# team_dashboard_display.net
KiCad netlist of a schematic drawn in EAGLE
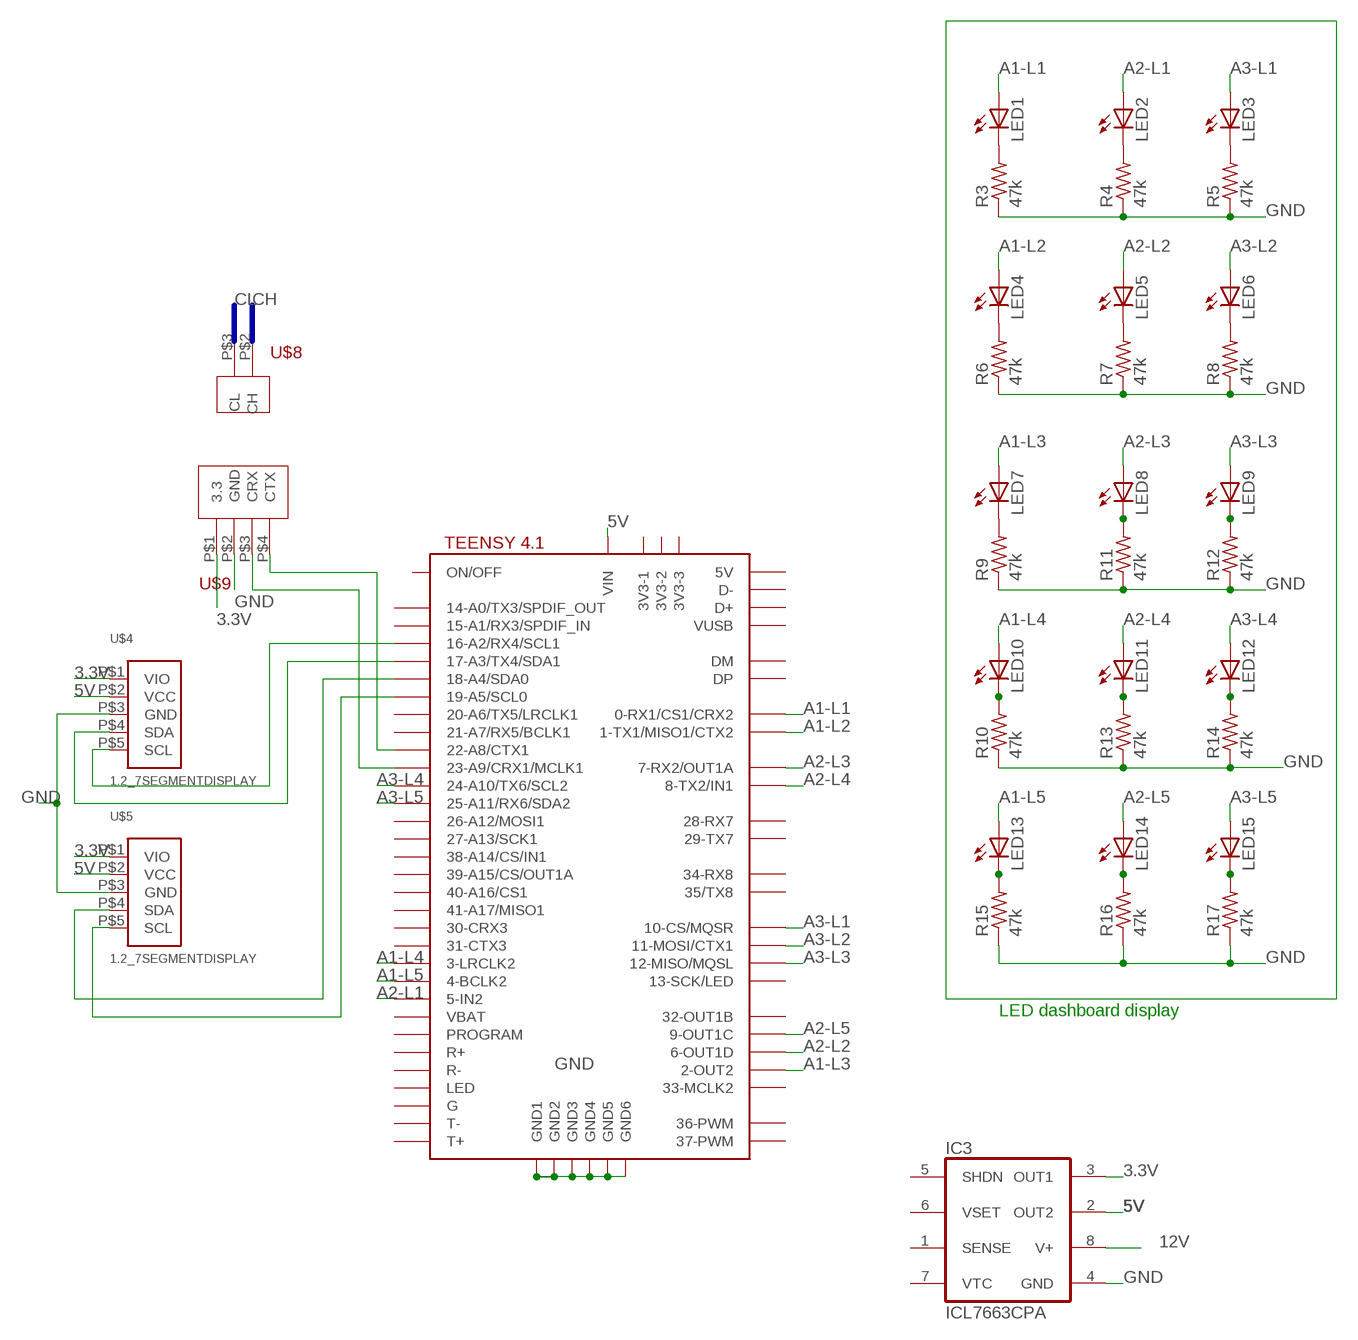
[diagram p0: schematic, sheet 1]

(export (version "E")
  (design (tool "Eeschema 10.0.6"))
  (components
    (comp (ref "IC3")
      (value "ICL7663CPA")
      (footprint "eagle-import:DIL08")
      (libsource (lib "eagle-import") (part "ICL7663CPA"))
    )
    (comp (ref "LED1")
      (value "LED3MM")
      (footprint "eagle-import:LED3MM")
      (libsource (lib "eagle-import") (part "LED3MM"))
    )
    (comp (ref "LED2")
      (value "LED3MM")
      (footprint "eagle-import:LED3MM")
      (libsource (lib "eagle-import") (part "LED3MM"))
    )
    (comp (ref "LED3")
      (value "LED3MM")
      (footprint "eagle-import:LED3MM")
      (libsource (lib "eagle-import") (part "LED3MM"))
    )
    (comp (ref "LED4")
      (value "LED3MM")
      (footprint "eagle-import:LED3MM")
      (libsource (lib "eagle-import") (part "LED3MM"))
    )
    (comp (ref "LED5")
      (value "LED3MM")
      (footprint "eagle-import:LED3MM")
      (libsource (lib "eagle-import") (part "LED3MM"))
    )
    (comp (ref "LED6")
      (value "LED3MM")
      (footprint "eagle-import:LED3MM")
      (libsource (lib "eagle-import") (part "LED3MM"))
    )
    (comp (ref "LED7")
      (value "LED3MM")
      (footprint "eagle-import:LED3MM")
      (libsource (lib "eagle-import") (part "LED3MM"))
    )
    (comp (ref "LED8")
      (value "LED3MM")
      (footprint "eagle-import:LED3MM")
      (libsource (lib "eagle-import") (part "LED3MM"))
    )
    (comp (ref "LED9")
      (value "LED3MM")
      (footprint "eagle-import:LED3MM")
      (libsource (lib "eagle-import") (part "LED3MM"))
    )
    (comp (ref "LED10")
      (value "LED3MM")
      (footprint "eagle-import:LED3MM")
      (libsource (lib "eagle-import") (part "LED3MM"))
    )
    (comp (ref "LED11")
      (value "LED3MM")
      (footprint "eagle-import:LED3MM")
      (libsource (lib "eagle-import") (part "LED3MM"))
    )
    (comp (ref "LED12")
      (value "LED3MM")
      (footprint "eagle-import:LED3MM")
      (libsource (lib "eagle-import") (part "LED3MM"))
    )
    (comp (ref "LED13")
      (value "LED3MM")
      (footprint "eagle-import:LED3MM")
      (libsource (lib "eagle-import") (part "LED3MM"))
    )
    (comp (ref "LED14")
      (value "LED3MM")
      (footprint "eagle-import:LED3MM")
      (libsource (lib "eagle-import") (part "LED3MM"))
    )
    (comp (ref "LED15")
      (value "LED3MM")
      (footprint "eagle-import:LED3MM")
      (libsource (lib "eagle-import") (part "LED3MM"))
    )
    (comp (ref "R3")
      (value "47k")
      (footprint "eagle-import:0204_7")
      (libsource (lib "eagle-import") (part "R-US_0204/7"))
    )
    (comp (ref "R4")
      (value "47k")
      (footprint "eagle-import:0204_7")
      (libsource (lib "eagle-import") (part "R-US_0204/7"))
    )
    (comp (ref "R5")
      (value "47k")
      (footprint "eagle-import:0204_7")
      (libsource (lib "eagle-import") (part "R-US_0204/7"))
    )
    (comp (ref "R6")
      (value "47k")
      (footprint "eagle-import:0204_7")
      (libsource (lib "eagle-import") (part "R-US_0204/7"))
    )
    (comp (ref "R7")
      (value "47k")
      (footprint "eagle-import:0204_7")
      (libsource (lib "eagle-import") (part "R-US_0204/7"))
    )
    (comp (ref "R8")
      (value "47k")
      (footprint "eagle-import:0204_7")
      (libsource (lib "eagle-import") (part "R-US_0204/7"))
    )
    (comp (ref "R9")
      (value "47k")
      (footprint "eagle-import:0204_7")
      (libsource (lib "eagle-import") (part "R-US_0204/7"))
    )
    (comp (ref "R10")
      (value "47k")
      (footprint "eagle-import:0204_7")
      (libsource (lib "eagle-import") (part "R-US_0204/7"))
    )
    (comp (ref "R11")
      (value "47k")
      (footprint "eagle-import:0204_7")
      (libsource (lib "eagle-import") (part "R-US_0204/7"))
    )
    (comp (ref "R12")
      (value "47k")
      (footprint "eagle-import:0204_7")
      (libsource (lib "eagle-import") (part "R-US_0204/7"))
    )
    (comp (ref "R13")
      (value "47k")
      (footprint "eagle-import:0204_7")
      (libsource (lib "eagle-import") (part "R-US_0204/7"))
    )
    (comp (ref "R14")
      (value "47k")
      (footprint "eagle-import:0204_7")
      (libsource (lib "eagle-import") (part "R-US_0204/7"))
    )
    (comp (ref "R15")
      (value "47k")
      (footprint "eagle-import:0204_7")
      (libsource (lib "eagle-import") (part "R-US_0204/7"))
    )
    (comp (ref "R16")
      (value "47k")
      (footprint "eagle-import:0204_7")
      (libsource (lib "eagle-import") (part "R-US_0204/7"))
    )
    (comp (ref "R17")
      (value "47k")
      (footprint "eagle-import:0204_7")
      (libsource (lib "eagle-import") (part "R-US_0204/7"))
    )
    (comp (ref "U$2")
      (value "TEENSY41")
      (footprint "eagle-import:TEENSY41")
      (libsource (lib "eagle-import") (part "TEENSY41"))
    )
    (comp (ref "U$4")
      (value "1.2_7SEGMENTDISPLAY")
      (footprint "eagle-import:5IL")
      (libsource (lib "eagle-import") (part "1.2_7SEGMENTDISPLAY"))
    )
    (comp (ref "U$5")
      (value "1.2_7SEGMENTDISPLAY")
      (footprint "eagle-import:5IL")
      (libsource (lib "eagle-import") (part "1.2_7SEGMENTDISPLAY"))
    )
    (comp (ref "U$8")
      (value "CAN_BUS")
      (footprint "eagle-import:CAN_BUS")
      (libsource (lib "eagle-import") (part "CAN_BUS"))
    )
    (comp (ref "U$9")
      (value "CAN_TEE")
      (footprint "eagle-import:CAN_TEN")
      (libsource (lib "eagle-import") (part "CAN_TEE"))
    )
  )
  (nets
    (net (code "3") (name "/3.3V") (class "Default")
      (node (ref "IC3") (pin "3") (pinfunction "OUT1_3") (pintype "output"))
      (node (ref "U$4") (pin "P$1") (pinfunction "VIO_P$1") (pintype "bidirectional"))
      (node (ref "U$5") (pin "P$1") (pinfunction "VIO_P$1") (pintype "bidirectional"))
      (node (ref "U$9") (pin "P$1") (pinfunction "3.3_P$1") (pintype "bidirectional"))
    )
    (net (code "4") (name "/5V") (class "Default")
      (node (ref "IC3") (pin "2") (pinfunction "OUT2_2") (pintype "output"))
      (node (ref "U$2") (pin "VIN") (pinfunction "VIN_VIN") (pintype "bidirectional"))
      (node (ref "U$4") (pin "P$2") (pinfunction "VCC_P$2") (pintype "bidirectional"))
      (node (ref "U$5") (pin "P$2") (pinfunction "VCC_P$2") (pintype "bidirectional"))
    )
    (net (code "5") (name "/12V") (class "Default")
      (node (ref "IC3") (pin "8") (pinfunction "V+_8") (pintype "power_in"))
    )
    (net (code "6") (name "/A1-L1") (class "Default")
      (node (ref "LED1") (pin "A") (pinfunction "A_A") (pintype "passive"))
      (node (ref "U$2") (pin "0-RX1/CS1/CRX2") (pinfunction "0-RX1/CS1/CRX2_0-RX1/CS1/CRX2") (pintype "bidirectional"))
    )
    (net (code "7") (name "/A1-L2") (class "Default")
      (node (ref "LED4") (pin "A") (pinfunction "A_A") (pintype "passive"))
      (node (ref "U$2") (pin "1-TX1/MISO1/CTX2") (pinfunction "1-TX1/MISO1/CTX2_1-TX1/MISO1/CTX2") (pintype "bidirectional"))
    )
    (net (code "8") (name "/A1-L3") (class "Default")
      (node (ref "LED7") (pin "A") (pinfunction "A_A") (pintype "passive"))
      (node (ref "U$2") (pin "2-OUT2") (pinfunction "2-OUT2_2-OUT2") (pintype "bidirectional"))
    )
    (net (code "9") (name "/A1-L4") (class "Default")
      (node (ref "LED10") (pin "A") (pinfunction "A_A") (pintype "passive"))
      (node (ref "U$2") (pin "3-LRCLK2") (pinfunction "3-LRCLK2_3-LRCLK2") (pintype "bidirectional"))
    )
    (net (code "10") (name "/A1-L5") (class "Default")
      (node (ref "LED13") (pin "A") (pinfunction "A_A") (pintype "passive"))
      (node (ref "U$2") (pin "4-BCLK2") (pinfunction "4-BCLK2_4-BCLK2") (pintype "bidirectional"))
    )
    (net (code "11") (name "/A2-L1") (class "Default")
      (node (ref "LED2") (pin "A") (pinfunction "A_A") (pintype "passive"))
      (node (ref "U$2") (pin "5-IN2") (pinfunction "5-IN2_5-IN2") (pintype "bidirectional"))
    )
    (net (code "12") (name "/A2-L2") (class "Default")
      (node (ref "LED5") (pin "A") (pinfunction "A_A") (pintype "passive"))
      (node (ref "U$2") (pin "6-OUT1D") (pinfunction "6-OUT1D_6-OUT1D") (pintype "bidirectional"))
    )
    (net (code "13") (name "/A2-L3") (class "Default")
      (node (ref "LED8") (pin "A") (pinfunction "A_A") (pintype "passive"))
      (node (ref "U$2") (pin "7-RX2/OUT1A") (pinfunction "7-RX2/OUT1A_7-RX2/OUT1A") (pintype "bidirectional"))
    )
    (net (code "14") (name "/A2-L4") (class "Default")
      (node (ref "LED11") (pin "A") (pinfunction "A_A") (pintype "passive"))
      (node (ref "U$2") (pin "8-TX2/IN2") (pinfunction "8-TX2/IN1_8-TX2/IN2") (pintype "bidirectional"))
    )
    (net (code "15") (name "/A2-L5") (class "Default")
      (node (ref "LED14") (pin "A") (pinfunction "A_A") (pintype "passive"))
      (node (ref "U$2") (pin "9-OUT1C") (pinfunction "9-OUT1C_9-OUT1C") (pintype "bidirectional"))
    )
    (net (code "16") (name "/A3-L1") (class "Default")
      (node (ref "LED3") (pin "A") (pinfunction "A_A") (pintype "passive"))
      (node (ref "U$2") (pin "10-CS\\MQSR") (pinfunction "10-CS/MQSR_10-CS\\MQSR") (pintype "bidirectional"))
    )
    (net (code "17") (name "/A3-L2") (class "Default")
      (node (ref "LED6") (pin "A") (pinfunction "A_A") (pintype "passive"))
      (node (ref "U$2") (pin "11-MOSI/CTX1") (pinfunction "11-MOSI/CTX1_11-MOSI/CTX1") (pintype "bidirectional"))
    )
    (net (code "18") (name "/A3-L3") (class "Default")
      (node (ref "LED9") (pin "A") (pinfunction "A_A") (pintype "passive"))
      (node (ref "U$2") (pin "12-MISO/MQSL") (pinfunction "12-MISO/MQSL_12-MISO/MQSL") (pintype "bidirectional"))
    )
    (net (code "19") (name "/A3-L4") (class "Default")
      (node (ref "LED12") (pin "A") (pinfunction "A_A") (pintype "passive"))
      (node (ref "U$2") (pin "24-A10/TX6/SCL2") (pinfunction "24-A10/TX6/SCL2_24-A10/TX6/SCL2") (pintype "bidirectional"))
    )
    (net (code "20") (name "/A3-L5") (class "Default")
      (node (ref "LED15") (pin "A") (pinfunction "A_A") (pintype "passive"))
      (node (ref "U$2") (pin "25-A11/RX6/SDA2") (pinfunction "25-A11/RX6/SDA2_25-A11/RX6/SDA2") (pintype "bidirectional"))
    )
    (net (code "21") (name "/GND") (class "Default")
      (node (ref "IC3") (pin "4") (pinfunction "GND_4") (pintype "power_in"))
      (node (ref "R10") (pin "1") (pinfunction "1_1") (pintype "passive"))
      (node (ref "R11") (pin "1") (pinfunction "1_1") (pintype "passive"))
      (node (ref "R12") (pin "1") (pinfunction "1_1") (pintype "passive"))
      (node (ref "R13") (pin "1") (pinfunction "1_1") (pintype "passive"))
      (node (ref "R14") (pin "1") (pinfunction "1_1") (pintype "passive"))
      (node (ref "R15") (pin "1") (pinfunction "1_1") (pintype "passive"))
      (node (ref "R16") (pin "1") (pinfunction "1_1") (pintype "passive"))
      (node (ref "R17") (pin "1") (pinfunction "1_1") (pintype "passive"))
      (node (ref "R3") (pin "1") (pinfunction "1_1") (pintype "passive"))
      (node (ref "R4") (pin "1") (pinfunction "1_1") (pintype "passive"))
      (node (ref "R5") (pin "1") (pinfunction "1_1") (pintype "passive"))
      (node (ref "R6") (pin "1") (pinfunction "1_1") (pintype "passive"))
      (node (ref "R7") (pin "1") (pinfunction "1_1") (pintype "passive"))
      (node (ref "R8") (pin "1") (pinfunction "1_1") (pintype "passive"))
      (node (ref "R9") (pin "1") (pinfunction "1_1") (pintype "passive"))
      (node (ref "U$2") (pin "GND1") (pinfunction "GND1_GND1") (pintype "bidirectional"))
      (node (ref "U$2") (pin "GND2") (pinfunction "GND2_GND2") (pintype "bidirectional"))
      (node (ref "U$2") (pin "GND3") (pinfunction "GND3_GND3") (pintype "bidirectional"))
      (node (ref "U$2") (pin "GND4") (pinfunction "GND4_GND4") (pintype "bidirectional"))
      (node (ref "U$2") (pin "GND5") (pinfunction "GND5_GND5") (pintype "bidirectional"))
      (node (ref "U$2") (pin "GND6") (pinfunction "GND6_GND6") (pintype "bidirectional"))
      (node (ref "U$4") (pin "P$3") (pinfunction "GND_P$3") (pintype "input"))
      (node (ref "U$5") (pin "P$3") (pinfunction "GND_P$3") (pintype "input"))
      (node (ref "U$9") (pin "P$2") (pinfunction "GND_P$2") (pintype "bidirectional"))
    )
    (net (code "22") (name "/{CH}") (class "Default")
      (node (ref "U$8") (pin "P$2") (pinfunction "CH_P$2") (pintype "bidirectional"))
    )
    (net (code "23") (name "/{CL}") (class "Default")
      (node (ref "U$8") (pin "P$3") (pinfunction "CL_P$3") (pintype "bidirectional"))
    )
    (net (code "24") (name "Net-(LED1-C)") (class "Default")
      (node (ref "LED1") (pin "K") (pinfunction "C_K") (pintype "passive"))
      (node (ref "R3") (pin "2") (pinfunction "2_2") (pintype "passive"))
    )
    (net (code "25") (name "Net-(LED2-C)") (class "Default")
      (node (ref "LED2") (pin "K") (pinfunction "C_K") (pintype "passive"))
      (node (ref "R4") (pin "2") (pinfunction "2_2") (pintype "passive"))
    )
    (net (code "26") (name "Net-(LED3-C)") (class "Default")
      (node (ref "LED3") (pin "K") (pinfunction "C_K") (pintype "passive"))
      (node (ref "R5") (pin "2") (pinfunction "2_2") (pintype "passive"))
    )
    (net (code "27") (name "Net-(LED4-C)") (class "Default")
      (node (ref "LED4") (pin "K") (pinfunction "C_K") (pintype "passive"))
      (node (ref "R6") (pin "2") (pinfunction "2_2") (pintype "passive"))
    )
    (net (code "28") (name "Net-(LED5-C)") (class "Default")
      (node (ref "LED5") (pin "K") (pinfunction "C_K") (pintype "passive"))
      (node (ref "R7") (pin "2") (pinfunction "2_2") (pintype "passive"))
    )
    (net (code "29") (name "Net-(LED6-C)") (class "Default")
      (node (ref "LED6") (pin "K") (pinfunction "C_K") (pintype "passive"))
      (node (ref "R8") (pin "2") (pinfunction "2_2") (pintype "passive"))
    )
    (net (code "30") (name "Net-(LED7-C)") (class "Default")
      (node (ref "LED7") (pin "K") (pinfunction "C_K") (pintype "passive"))
      (node (ref "R9") (pin "2") (pinfunction "2_2") (pintype "passive"))
    )
    (net (code "31") (name "Net-(LED8-C)") (class "Default")
      (node (ref "LED8") (pin "K") (pinfunction "C_K") (pintype "passive"))
      (node (ref "R11") (pin "2") (pinfunction "2_2") (pintype "passive"))
    )
    (net (code "32") (name "Net-(LED9-C)") (class "Default")
      (node (ref "LED9") (pin "K") (pinfunction "C_K") (pintype "passive"))
      (node (ref "R12") (pin "2") (pinfunction "2_2") (pintype "passive"))
    )
    (net (code "33") (name "Net-(LED10-C)") (class "Default")
      (node (ref "LED10") (pin "K") (pinfunction "C_K") (pintype "passive"))
      (node (ref "R10") (pin "2") (pinfunction "2_2") (pintype "passive"))
    )
    (net (code "34") (name "Net-(LED11-C)") (class "Default")
      (node (ref "LED11") (pin "K") (pinfunction "C_K") (pintype "passive"))
      (node (ref "R13") (pin "2") (pinfunction "2_2") (pintype "passive"))
    )
    (net (code "35") (name "Net-(LED12-C)") (class "Default")
      (node (ref "LED12") (pin "K") (pinfunction "C_K") (pintype "passive"))
      (node (ref "R14") (pin "2") (pinfunction "2_2") (pintype "passive"))
    )
    (net (code "36") (name "Net-(LED13-C)") (class "Default")
      (node (ref "LED13") (pin "K") (pinfunction "C_K") (pintype "passive"))
      (node (ref "R15") (pin "2") (pinfunction "2_2") (pintype "passive"))
    )
    (net (code "37") (name "Net-(LED14-C)") (class "Default")
      (node (ref "LED14") (pin "K") (pinfunction "C_K") (pintype "passive"))
      (node (ref "R16") (pin "2") (pinfunction "2_2") (pintype "passive"))
    )
    (net (code "38") (name "Net-(LED15-C)") (class "Default")
      (node (ref "LED15") (pin "K") (pinfunction "C_K") (pintype "passive"))
      (node (ref "R17") (pin "2") (pinfunction "2_2") (pintype "passive"))
    )
    (net (code "39") (name "Net-(U$4-SCL)") (class "Default")
      (node (ref "U$2") (pin "16-A2/RX4/SCL1") (pinfunction "16-A2/RX4/SCL1_16-A2/RX4/SCL1") (pintype "bidirectional"))
      (node (ref "U$4") (pin "P$5") (pinfunction "SCL_P$5") (pintype "bidirectional"))
    )
    (net (code "40") (name "Net-(U$4-SDA)") (class "Default")
      (node (ref "U$2") (pin "17-A3/TX4/SDA1") (pinfunction "17-A3/TX4/SDA1_17-A3/TX4/SDA1") (pintype "bidirectional"))
      (node (ref "U$4") (pin "P$4") (pinfunction "SDA_P$4") (pintype "bidirectional"))
    )
    (net (code "41") (name "Net-(U$5-SCL)") (class "Default")
      (node (ref "U$2") (pin "19-A5/SCL0") (pinfunction "19-A5/SCL0_19-A5/SCL0") (pintype "bidirectional"))
      (node (ref "U$5") (pin "P$5") (pinfunction "SCL_P$5") (pintype "bidirectional"))
    )
    (net (code "42") (name "Net-(U$5-SDA)") (class "Default")
      (node (ref "U$2") (pin "18-A4/SDA0") (pinfunction "18-A4/SDA0_18-A4/SDA0") (pintype "bidirectional"))
      (node (ref "U$5") (pin "P$4") (pinfunction "SDA_P$4") (pintype "bidirectional"))
    )
    (net (code "43") (name "Net-(U$9-CRX)") (class "Default")
      (node (ref "U$2") (pin "23-A9/CRX1/MCLK1") (pinfunction "23-A9/CRX1/MCLK1_23-A9/CRX1/MCLK1") (pintype "bidirectional"))
      (node (ref "U$9") (pin "P$3") (pinfunction "CRX_P$3") (pintype "bidirectional"))
    )
    (net (code "44") (name "Net-(U$9-CTX)") (class "Default")
      (node (ref "U$2") (pin "22-A8/CTX1") (pinfunction "22-A8/CTX1_22-A8/CTX1") (pintype "bidirectional"))
      (node (ref "U$9") (pin "P$4") (pinfunction "CTX_P$4") (pintype "bidirectional"))
    )
    (net (code "45") (name "unconnected-(IC3-SENSE-Pad1)") (class "Default")
      (node (ref "IC3") (pin "1") (pinfunction "SENSE_1") (pintype "input"))
    )
    (net (code "46") (name "unconnected-(IC3-SHDN-Pad5)") (class "Default")
      (node (ref "IC3") (pin "5") (pinfunction "SHDN_5") (pintype "input"))
    )
    (net (code "47") (name "unconnected-(IC3-VSET-Pad6)") (class "Default")
      (node (ref "IC3") (pin "6") (pinfunction "VSET_6") (pintype "input"))
    )
    (net (code "48") (name "unconnected-(IC3-VTC-Pad7)") (class "Default")
      (node (ref "IC3") (pin "7") (pinfunction "VTC_7") (pintype "passive"))
    )
    (net (code "49") (name "unconnected-(U$2-5V-Pad+5V)") (class "Default")
      (node (ref "U$2") (pin "+5V") (pinfunction "5V_+5V") (pintype "bidirectional"))
    )
    (net (code "50") (name "unconnected-(U$2-35{slash}TX8-Pad35-TX8)") (class "Default")
      (node (ref "U$2") (pin "35-TX8") (pinfunction "35/TX8_35-TX8") (pintype "bidirectional"))
    )
    (net (code "51") (name "unconnected-(U$2-Pad3V3-1)") (class "Default")
      (node (ref "U$2") (pin "3V3-1") (pinfunction "3V3-1_3V3-1") (pintype "bidirectional"))
    )
    (net (code "52") (name "unconnected-(U$2-Pad3V3-2)") (class "Default")
      (node (ref "U$2") (pin "3V3-2") (pinfunction "3V3-2_3V3-2") (pintype "bidirectional"))
    )
    (net (code "53") (name "unconnected-(U$2-Pad3V3-3)") (class "Default")
      (node (ref "U$2") (pin "3V3-3") (pinfunction "3V3-3_3V3-3") (pintype "bidirectional"))
    )
    (net (code "54") (name "unconnected-(U$2-Pad13-SCK{slash}LED)") (class "Default")
      (node (ref "U$2") (pin "13-SCK/LED") (pinfunction "13-SCK/LED_13-SCK/LED") (pintype "bidirectional"))
    )
    (net (code "55") (name "unconnected-(U$2-Pad14-A0{slash}TX3{slash}SPDIF_OUT)") (class "Default")
      (node (ref "U$2") (pin "14-A0/TX3/SPDIF_OUT") (pinfunction "14-A0/TX3/SPDIF_OUT_14-A0/TX3/SPDIF_OUT") (pintype "bidirectional"))
    )
    (net (code "56") (name "unconnected-(U$2-Pad15-A1{slash}RX3{slash}SPDIF_IN)") (class "Default")
      (node (ref "U$2") (pin "15-A1/RX3/SPDIF_IN") (pinfunction "15-A1/RX3/SPDIF_IN_15-A1/RX3/SPDIF_IN") (pintype "bidirectional"))
    )
    (net (code "57") (name "unconnected-(U$2-Pad20-A6{slash}TX5{slash}LRCLK1)") (class "Default")
      (node (ref "U$2") (pin "20-A6/TX5/LRCLK1") (pinfunction "20-A6/TX5/LRCLK1_20-A6/TX5/LRCLK1") (pintype "bidirectional"))
    )
    (net (code "58") (name "unconnected-(U$2-Pad21-A7{slash}RX5{slash}BCLK1)") (class "Default")
      (node (ref "U$2") (pin "21-A7/RX5/BCLK1") (pinfunction "21-A7/RX5/BCLK1_21-A7/RX5/BCLK1") (pintype "bidirectional"))
    )
    (net (code "59") (name "unconnected-(U$2-Pad26-A12{slash}MOSI1)") (class "Default")
      (node (ref "U$2") (pin "26-A12/MOSI1") (pinfunction "26-A12/MOSI1_26-A12/MOSI1") (pintype "bidirectional"))
    )
    (net (code "60") (name "unconnected-(U$2-Pad27-A13{slash}SCK1)") (class "Default")
      (node (ref "U$2") (pin "27-A13/SCK1") (pinfunction "27-A13/SCK1_27-A13/SCK1") (pintype "bidirectional"))
    )
    (net (code "61") (name "unconnected-(U$2-Pad28-RX7)") (class "Default")
      (node (ref "U$2") (pin "28-RX7") (pinfunction "28-RX7_28-RX7") (pintype "bidirectional"))
    )
    (net (code "62") (name "unconnected-(U$2-Pad29-TX7)") (class "Default")
      (node (ref "U$2") (pin "29-TX7") (pinfunction "29-TX7_29-TX7") (pintype "bidirectional"))
    )
    (net (code "63") (name "unconnected-(U$2-Pad30-CRX3)") (class "Default")
      (node (ref "U$2") (pin "30-CRX3") (pinfunction "30-CRX3_30-CRX3") (pintype "bidirectional"))
    )
    (net (code "64") (name "unconnected-(U$2-Pad31-CTX3)") (class "Default")
      (node (ref "U$2") (pin "31-CTX3") (pinfunction "31-CTX3_31-CTX3") (pintype "bidirectional"))
    )
    (net (code "65") (name "unconnected-(U$2-Pad32-OUT1B)") (class "Default")
      (node (ref "U$2") (pin "32-OUT1B") (pinfunction "32-OUT1B_32-OUT1B") (pintype "bidirectional"))
    )
    (net (code "66") (name "unconnected-(U$2-Pad33-MCLK2)") (class "Default")
      (node (ref "U$2") (pin "33-MCLK2") (pinfunction "33-MCLK2_33-MCLK2") (pintype "bidirectional"))
    )
    (net (code "67") (name "unconnected-(U$2-Pad34-RX8)") (class "Default")
      (node (ref "U$2") (pin "34-RX8") (pinfunction "34-RX8_34-RX8") (pintype "bidirectional"))
    )
    (net (code "68") (name "unconnected-(U$2-Pad36-PWM)") (class "Default")
      (node (ref "U$2") (pin "36-PWM") (pinfunction "36-PWM_36-PWM") (pintype "bidirectional"))
    )
    (net (code "69") (name "unconnected-(U$2-Pad37-PWM)") (class "Default")
      (node (ref "U$2") (pin "37-PWM") (pinfunction "37-PWM_37-PWM") (pintype "bidirectional"))
    )
    (net (code "70") (name "unconnected-(U$2-Pad38-A14{slash}CS{slash}IN1)") (class "Default")
      (node (ref "U$2") (pin "38-A14/CS/IN1") (pinfunction "38-A14/CS/IN1_38-A14/CS/IN1") (pintype "bidirectional"))
    )
    (net (code "71") (name "unconnected-(U$2-Pad39-A15{slash}CS{slash}OUT1A)") (class "Default")
      (node (ref "U$2") (pin "39-A15/CS/OUT1A") (pinfunction "39-A15/CS/OUT1A_39-A15/CS/OUT1A") (pintype "bidirectional"))
    )
    (net (code "72") (name "unconnected-(U$2-Pad40-A16{slash}CS1)") (class "Default")
      (node (ref "U$2") (pin "40-A16/CS1") (pinfunction "40-A16/CS1_40-A16/CS1") (pintype "bidirectional"))
    )
    (net (code "73") (name "unconnected-(U$2-Pad41-A17{slash}MISO1)") (class "Default")
      (node (ref "U$2") (pin "41-A17/MISO1") (pinfunction "41-A17/MISO1_41-A17/MISO1") (pintype "bidirectional"))
    )
    (net (code "74") (name "unconnected-(U$2-PadD+)") (class "Default")
      (node (ref "U$2") (pin "D+") (pinfunction "D+_D+") (pintype "bidirectional"))
    )
    (net (code "75") (name "unconnected-(U$2-PadD-)") (class "Default")
      (node (ref "U$2") (pin "D-") (pinfunction "D-_D-") (pintype "bidirectional"))
    )
    (net (code "76") (name "unconnected-(U$2-PadDM)") (class "Default")
      (node (ref "U$2") (pin "DM") (pinfunction "DM_DM") (pintype "bidirectional"))
    )
    (net (code "77") (name "unconnected-(U$2-PadDP)") (class "Default")
      (node (ref "U$2") (pin "DP") (pinfunction "DP_DP") (pintype "bidirectional"))
    )
    (net (code "78") (name "unconnected-(U$2-PadG)") (class "Default")
      (node (ref "U$2") (pin "G") (pinfunction "G_G") (pintype "bidirectional"))
    )
    (net (code "79") (name "unconnected-(U$2-PadLED)") (class "Default")
      (node (ref "U$2") (pin "LED") (pinfunction "LED_LED") (pintype "bidirectional"))
    )
    (net (code "80") (name "unconnected-(U$2-PadON{slash}OFF)") (class "Default")
      (node (ref "U$2") (pin "ON/OFF") (pinfunction "ON/OFF_ON/OFF") (pintype "bidirectional"))
    )
    (net (code "81") (name "unconnected-(U$2-PadPROGRAM)") (class "Default")
      (node (ref "U$2") (pin "PROGRAM") (pinfunction "PROGRAM_PROGRAM") (pintype "bidirectional"))
    )
    (net (code "82") (name "unconnected-(U$2-PadR+)") (class "Default")
      (node (ref "U$2") (pin "R+") (pinfunction "R+_R+") (pintype "bidirectional"))
    )
    (net (code "83") (name "unconnected-(U$2-PadR-)") (class "Default")
      (node (ref "U$2") (pin "R-") (pinfunction "R-_R-") (pintype "bidirectional"))
    )
    (net (code "84") (name "unconnected-(U$2-PadT+)") (class "Default")
      (node (ref "U$2") (pin "T+") (pinfunction "T+_T+") (pintype "bidirectional"))
    )
    (net (code "85") (name "unconnected-(U$2-PadT-)") (class "Default")
      (node (ref "U$2") (pin "T-") (pinfunction "T-_T-") (pintype "bidirectional"))
    )
    (net (code "86") (name "unconnected-(U$2-PadVBAT)") (class "Default")
      (node (ref "U$2") (pin "VBAT") (pinfunction "VBAT_VBAT") (pintype "bidirectional"))
    )
    (net (code "87") (name "unconnected-(U$2-PadVUSB)") (class "Default")
      (node (ref "U$2") (pin "VUSB") (pinfunction "VUSB_VUSB") (pintype "bidirectional"))
    )
  )
)
